# Parallel.net
KiCad netlist of a schematic drawn in EAGLE
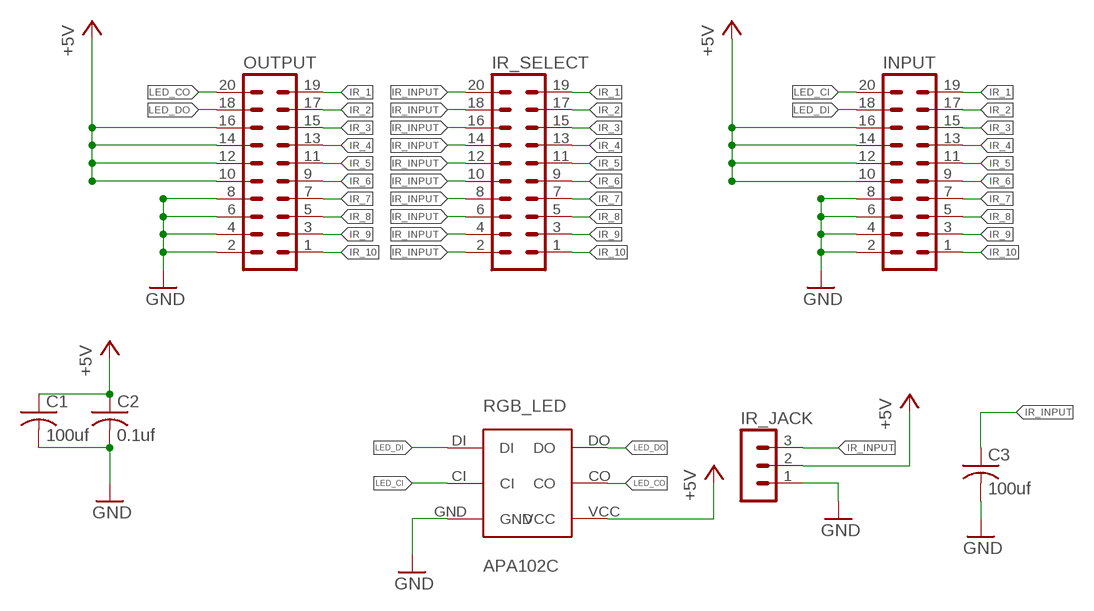
[diagram p0: schematic, sheet 1]

(export (version "E")
  (design (tool "Eeschema 10.0.6"))
  (components
    (comp (ref "C1")
      (value "100uf")
      (footprint "eagle-import:C0805")
      (libsource (lib "eagle-import") (part "C-USC0805"))
    )
    (comp (ref "C2")
      (value "0.1uf")
      (footprint "eagle-import:C0603")
      (libsource (lib "eagle-import") (part "C-USC0603"))
    )
    (comp (ref "C3")
      (value "100uf")
      (footprint "eagle-import:C0805")
      (libsource (lib "eagle-import") (part "C-USC0805"))
    )
    (comp (ref "INPUT")
      (value "MA10-2")
      (footprint "eagle-import:MA10-2")
      (libsource (lib "eagle-import") (part "MA10-2"))
    )
    (comp (ref "IR_JACK")
      (value "MA03-1")
      (footprint "eagle-import:MA03-1")
      (libsource (lib "eagle-import") (part "MA03-1"))
    )
    (comp (ref "IR_SELECT")
      (value "MA10-2")
      (footprint "eagle-import:MA10-2")
      (libsource (lib "eagle-import") (part "MA10-2"))
    )
    (comp (ref "OUTPUT")
      (value "MA10-2")
      (footprint "eagle-import:MA10-2")
      (libsource (lib "eagle-import") (part "MA10-2"))
    )
    (comp (ref "RGB_LED")
      (value "APA102C")
      (footprint "eagle-import:APA102C")
      (libsource (lib "eagle-import") (part "APA102C"))
    )
  )
  (nets
    (net (code "1") (name "+5V") (class "Default")
      (node (ref "C1") (pin "1") (pinfunction "1_1") (pintype "passive"))
      (node (ref "C2") (pin "1") (pinfunction "1_1") (pintype "passive"))
      (node (ref "INPUT") (pin "10") (pinfunction "10_10") (pintype "passive"))
      (node (ref "INPUT") (pin "12") (pinfunction "12_12") (pintype "passive"))
      (node (ref "INPUT") (pin "14") (pinfunction "14_14") (pintype "passive"))
      (node (ref "INPUT") (pin "16") (pinfunction "16_16") (pintype "passive"))
      (node (ref "IR_JACK") (pin "2") (pinfunction "2_2") (pintype "passive"))
      (node (ref "OUTPUT") (pin "10") (pinfunction "10_10") (pintype "passive"))
      (node (ref "OUTPUT") (pin "12") (pinfunction "12_12") (pintype "passive"))
      (node (ref "OUTPUT") (pin "14") (pinfunction "14_14") (pintype "passive"))
      (node (ref "OUTPUT") (pin "16") (pinfunction "16_16") (pintype "passive"))
      (node (ref "RGB_LED") (pin "VCC") (pinfunction "VCC_VCC") (pintype "bidirectional"))
    )
    (net (code "2") (name "GND") (class "Default")
      (node (ref "C1") (pin "2") (pinfunction "2_2") (pintype "passive"))
      (node (ref "C2") (pin "2") (pinfunction "2_2") (pintype "passive"))
      (node (ref "C3") (pin "2") (pinfunction "2_2") (pintype "passive"))
      (node (ref "INPUT") (pin "2") (pinfunction "2_2") (pintype "passive"))
      (node (ref "INPUT") (pin "4") (pinfunction "4_4") (pintype "passive"))
      (node (ref "INPUT") (pin "6") (pinfunction "6_6") (pintype "passive"))
      (node (ref "INPUT") (pin "8") (pinfunction "8_8") (pintype "passive"))
      (node (ref "IR_JACK") (pin "1") (pinfunction "1_1") (pintype "passive"))
      (node (ref "OUTPUT") (pin "2") (pinfunction "2_2") (pintype "passive"))
      (node (ref "OUTPUT") (pin "4") (pinfunction "4_4") (pintype "passive"))
      (node (ref "OUTPUT") (pin "6") (pinfunction "6_6") (pintype "passive"))
      (node (ref "OUTPUT") (pin "8") (pinfunction "8_8") (pintype "passive"))
      (node (ref "RGB_LED") (pin "GND") (pinfunction "GND_GND") (pintype "bidirectional"))
    )
    (net (code "3") (name "IR_1") (class "Default")
      (node (ref "INPUT") (pin "19") (pinfunction "19_19") (pintype "passive"))
      (node (ref "IR_SELECT") (pin "19") (pinfunction "19_19") (pintype "passive"))
      (node (ref "OUTPUT") (pin "19") (pinfunction "19_19") (pintype "passive"))
    )
    (net (code "4") (name "IR_2") (class "Default")
      (node (ref "INPUT") (pin "17") (pinfunction "17_17") (pintype "passive"))
      (node (ref "IR_SELECT") (pin "17") (pinfunction "17_17") (pintype "passive"))
      (node (ref "OUTPUT") (pin "17") (pinfunction "17_17") (pintype "passive"))
    )
    (net (code "5") (name "IR_3") (class "Default")
      (node (ref "INPUT") (pin "15") (pinfunction "15_15") (pintype "passive"))
      (node (ref "IR_SELECT") (pin "15") (pinfunction "15_15") (pintype "passive"))
      (node (ref "OUTPUT") (pin "15") (pinfunction "15_15") (pintype "passive"))
    )
    (net (code "6") (name "IR_4") (class "Default")
      (node (ref "INPUT") (pin "13") (pinfunction "13_13") (pintype "passive"))
      (node (ref "IR_SELECT") (pin "13") (pinfunction "13_13") (pintype "passive"))
      (node (ref "OUTPUT") (pin "13") (pinfunction "13_13") (pintype "passive"))
    )
    (net (code "7") (name "IR_5") (class "Default")
      (node (ref "INPUT") (pin "11") (pinfunction "11_11") (pintype "passive"))
      (node (ref "IR_SELECT") (pin "11") (pinfunction "11_11") (pintype "passive"))
      (node (ref "OUTPUT") (pin "11") (pinfunction "11_11") (pintype "passive"))
    )
    (net (code "8") (name "IR_6") (class "Default")
      (node (ref "INPUT") (pin "9") (pinfunction "9_9") (pintype "passive"))
      (node (ref "IR_SELECT") (pin "9") (pinfunction "9_9") (pintype "passive"))
      (node (ref "OUTPUT") (pin "9") (pinfunction "9_9") (pintype "passive"))
    )
    (net (code "9") (name "IR_7") (class "Default")
      (node (ref "INPUT") (pin "7") (pinfunction "7_7") (pintype "passive"))
      (node (ref "IR_SELECT") (pin "7") (pinfunction "7_7") (pintype "passive"))
      (node (ref "OUTPUT") (pin "7") (pinfunction "7_7") (pintype "passive"))
    )
    (net (code "10") (name "IR_8") (class "Default")
      (node (ref "INPUT") (pin "5") (pinfunction "5_5") (pintype "passive"))
      (node (ref "IR_SELECT") (pin "5") (pinfunction "5_5") (pintype "passive"))
      (node (ref "OUTPUT") (pin "5") (pinfunction "5_5") (pintype "passive"))
    )
    (net (code "11") (name "IR_9") (class "Default")
      (node (ref "INPUT") (pin "3") (pinfunction "3_3") (pintype "passive"))
      (node (ref "IR_SELECT") (pin "3") (pinfunction "3_3") (pintype "passive"))
      (node (ref "OUTPUT") (pin "3") (pinfunction "3_3") (pintype "passive"))
    )
    (net (code "12") (name "IR_10") (class "Default")
      (node (ref "INPUT") (pin "1") (pinfunction "1_1") (pintype "passive"))
      (node (ref "IR_SELECT") (pin "1") (pinfunction "1_1") (pintype "passive"))
      (node (ref "OUTPUT") (pin "1") (pinfunction "1_1") (pintype "passive"))
    )
    (net (code "13") (name "IR_INPUT") (class "Default")
      (node (ref "C3") (pin "1") (pinfunction "1_1") (pintype "passive"))
      (node (ref "IR_JACK") (pin "3") (pinfunction "3_3") (pintype "passive"))
      (node (ref "IR_SELECT") (pin "10") (pinfunction "10_10") (pintype "passive"))
      (node (ref "IR_SELECT") (pin "12") (pinfunction "12_12") (pintype "passive"))
      (node (ref "IR_SELECT") (pin "14") (pinfunction "14_14") (pintype "passive"))
      (node (ref "IR_SELECT") (pin "16") (pinfunction "16_16") (pintype "passive"))
      (node (ref "IR_SELECT") (pin "18") (pinfunction "18_18") (pintype "passive"))
      (node (ref "IR_SELECT") (pin "2") (pinfunction "2_2") (pintype "passive"))
      (node (ref "IR_SELECT") (pin "20") (pinfunction "20_20") (pintype "passive"))
      (node (ref "IR_SELECT") (pin "4") (pinfunction "4_4") (pintype "passive"))
      (node (ref "IR_SELECT") (pin "6") (pinfunction "6_6") (pintype "passive"))
      (node (ref "IR_SELECT") (pin "8") (pinfunction "8_8") (pintype "passive"))
    )
    (net (code "14") (name "LED_CI") (class "Default")
      (node (ref "INPUT") (pin "20") (pinfunction "20_20") (pintype "passive"))
      (node (ref "RGB_LED") (pin "CI") (pinfunction "CI_CI") (pintype "bidirectional"))
    )
    (net (code "15") (name "LED_CO") (class "Default")
      (node (ref "OUTPUT") (pin "20") (pinfunction "20_20") (pintype "passive"))
      (node (ref "RGB_LED") (pin "CO") (pinfunction "CO_CO") (pintype "bidirectional"))
    )
    (net (code "16") (name "LED_DI") (class "Default")
      (node (ref "INPUT") (pin "18") (pinfunction "18_18") (pintype "passive"))
      (node (ref "RGB_LED") (pin "DI") (pinfunction "DI_DI") (pintype "bidirectional"))
    )
    (net (code "17") (name "LED_DO") (class "Default")
      (node (ref "OUTPUT") (pin "18") (pinfunction "18_18") (pintype "passive"))
      (node (ref "RGB_LED") (pin "DO") (pinfunction "DO_DO") (pintype "bidirectional"))
    )
  )
)
